# MPU9250_Adapter.net
KiCad netlist of a schematic drawn in EAGLE
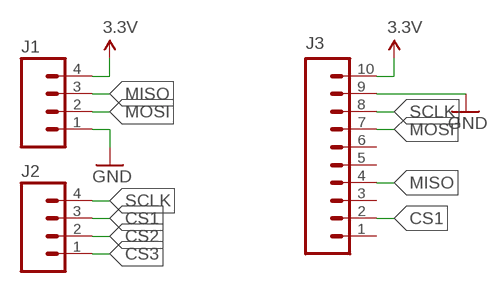
[diagram p0: schematic, sheet 1]

(export (version "E")
  (design (tool "Eeschema 10.0.6"))
  (components
    (comp (ref "J1")
      (value "M04PTH")
      (footprint "eagle-import:1X04")
      (libsource (lib "eagle-import") (part "M04PTH"))
    )
    (comp (ref "J2")
      (value "M04PTH")
      (footprint "eagle-import:1X04")
      (libsource (lib "eagle-import") (part "M04PTH"))
    )
    (comp (ref "J3")
      (value "M10SILK_FEMALE_PTH")
      (footprint "eagle-import:1X10")
      (libsource (lib "eagle-import") (part "M10SILK_FEMALE_PTH"))
    )
  )
  (nets
    (net (code "1") (name "3.3V") (class "Default")
      (node (ref "J1") (pin "4") (pinfunction "4_4") (pintype "passive"))
      (node (ref "J3") (pin "10") (pinfunction "10_10") (pintype "passive"))
    )
    (net (code "2") (name "CS1") (class "Default")
      (node (ref "J2") (pin "3") (pinfunction "3_3") (pintype "passive"))
      (node (ref "J3") (pin "2") (pinfunction "2_2") (pintype "passive"))
    )
    (net (code "3") (name "CS2") (class "Default")
      (node (ref "J2") (pin "2") (pinfunction "2_2") (pintype "passive"))
    )
    (net (code "4") (name "CS3") (class "Default")
      (node (ref "J2") (pin "1") (pinfunction "1_1") (pintype "passive"))
    )
    (net (code "5") (name "GND") (class "Default")
      (node (ref "J1") (pin "1") (pinfunction "1_1") (pintype "passive"))
      (node (ref "J3") (pin "9") (pinfunction "9_9") (pintype "passive"))
    )
    (net (code "6") (name "MISO") (class "Default")
      (node (ref "J1") (pin "3") (pinfunction "3_3") (pintype "passive"))
      (node (ref "J3") (pin "4") (pinfunction "4_4") (pintype "passive"))
    )
    (net (code "7") (name "MOSI") (class "Default")
      (node (ref "J1") (pin "2") (pinfunction "2_2") (pintype "passive"))
      (node (ref "J3") (pin "7") (pinfunction "7_7") (pintype "passive"))
    )
    (net (code "8") (name "SCLK") (class "Default")
      (node (ref "J2") (pin "4") (pinfunction "4_4") (pintype "passive"))
      (node (ref "J3") (pin "8") (pinfunction "8_8") (pintype "passive"))
    )
    (net (code "9") (name "unconnected-(J3-Pad1)") (class "Default")
      (node (ref "J3") (pin "1") (pinfunction "1_1") (pintype "passive"))
    )
    (net (code "10") (name "unconnected-(J3-Pad3)") (class "Default")
      (node (ref "J3") (pin "3") (pinfunction "3_3") (pintype "passive"))
    )
    (net (code "11") (name "unconnected-(J3-Pad5)") (class "Default")
      (node (ref "J3") (pin "5") (pinfunction "5_5") (pintype "passive"))
    )
    (net (code "12") (name "unconnected-(J3-Pad6)") (class "Default")
      (node (ref "J3") (pin "6") (pinfunction "6_6") (pintype "passive"))
    )
  )
)
